# epaper-watch.net
KiCad netlist of a schematic drawn in EAGLE
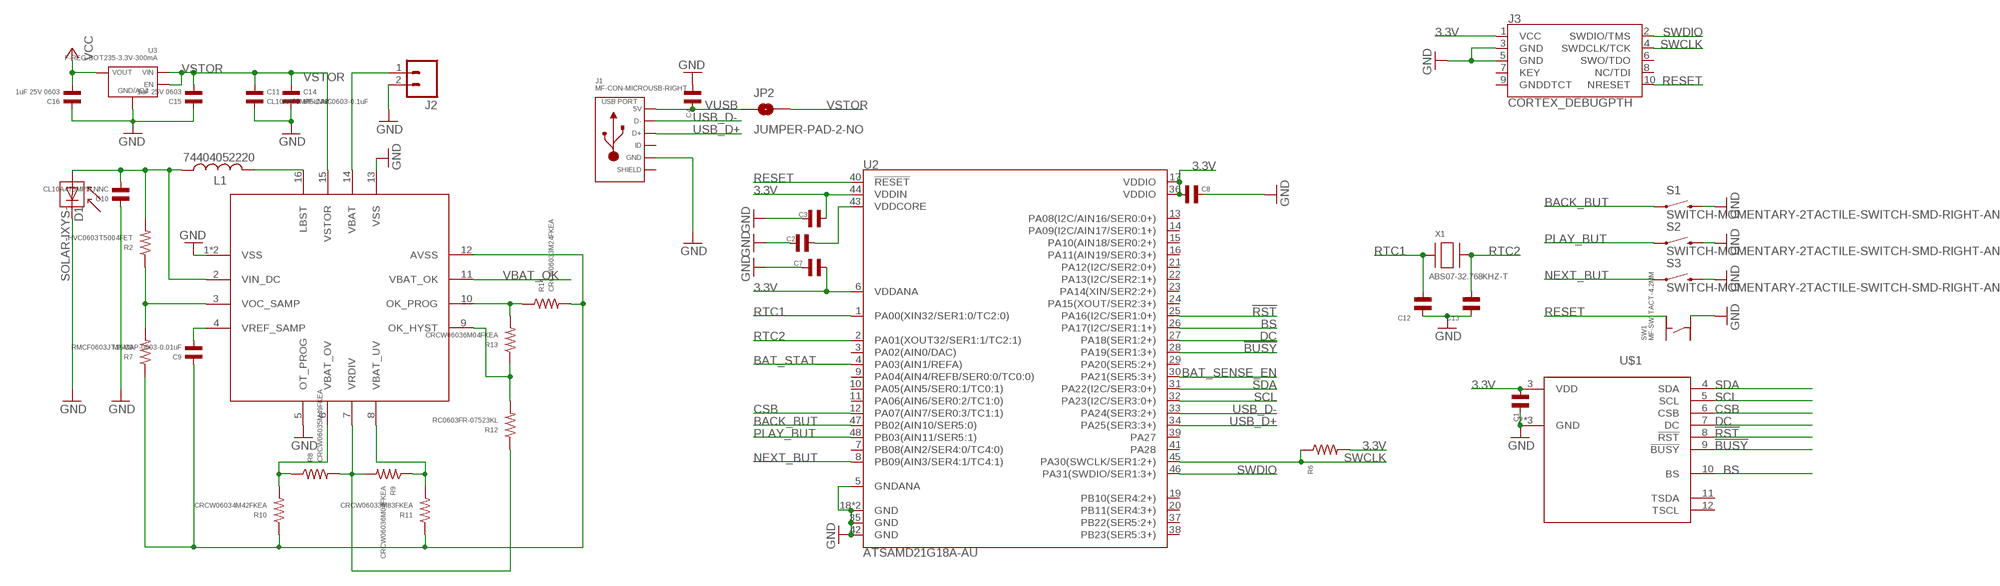
[diagram p0: schematic, sheet 1]

(export (version "E")
  (design (tool "Eeschema 10.0.6"))
  (components
    (comp (ref "C1")
      (value "0.1uF 0603")
      (footprint "eagle-import:C0603")
      (libsource (lib "eagle-import") (part "CAPACITOR_NP_0603"))
    )
    (comp (ref "C2")
      (value "1uF 0603")
      (footprint "eagle-import:C0603")
      (libsource (lib "eagle-import") (part "CAPACITOR_NP_0603"))
    )
    (comp (ref "C3")
      (value "0.1uF 0603")
      (footprint "eagle-import:C0603")
      (libsource (lib "eagle-import") (part "CAPACITOR_NP_0603"))
    )
    (comp (ref "C4")
      (value "0.1uF 0603")
      (footprint "eagle-import:C0603")
      (libsource (lib "eagle-import") (part "CAPACITOR_NP_0603"))
    )
    (comp (ref "C7")
      (value "0.1uF 0603")
      (footprint "eagle-import:C0603")
      (libsource (lib "eagle-import") (part "CAPACITOR_NP_0603"))
    )
    (comp (ref "C8")
      (value "0.1uF 0603")
      (footprint "eagle-import:C0603")
      (libsource (lib "eagle-import") (part "CAPACITOR_NP_0603"))
    )
    (comp (ref "C9")
      (value "MF-CAP-0603-0.01uF")
      (footprint "eagle-import:C0603")
      (libsource (lib "eagle-import") (part "CAPACITOR_NP_0603"))
    )
    (comp (ref "C10")
      (value "CL10A475MP5LNNC")
      (footprint "eagle-import:C0603")
      (libsource (lib "eagle-import") (part "CAPACITOR_NP_0603"))
    )
    (comp (ref "C11")
      (value "CL10A475MP5LNNC")
      (footprint "eagle-import:C0603")
      (libsource (lib "eagle-import") (part "CAPACITOR_NP_0603"))
    )
    (comp (ref "C12")
      (value "15pF")
      (footprint "eagle-import:C0603")
      (libsource (lib "eagle-import") (part "CAPACITOR_NP_0603"))
    )
    (comp (ref "C13")
      (value "15pF")
      (footprint "eagle-import:C0603")
      (libsource (lib "eagle-import") (part "CAPACITOR_NP_0603"))
    )
    (comp (ref "C14")
      (value "MF-CAP-0603-0.1uF")
      (footprint "eagle-import:C0603")
      (libsource (lib "eagle-import") (part "CAPACITOR_NP_0603"))
    )
    (comp (ref "C15")
      (value "1uF 25V 0603")
      (footprint "eagle-import:C0603")
      (libsource (lib "eagle-import") (part "CAPACITOR_NP_0603"))
    )
    (comp (ref "C16")
      (value "1uF 25V 0603")
      (footprint "eagle-import:C0603")
      (libsource (lib "eagle-import") (part "CAPACITOR_NP_0603"))
    )
    (comp (ref "D1")
      (value "SOLAR-IXYS-")
      (footprint "eagle-import:SOLARBIT-12X1")
      (libsource (lib "eagle-import") (part "SOLAR-IXYS-"))
    )
    (comp (ref "J1")
      (value "MF-CON-MICROUSB-RIGHT")
      (footprint "eagle-import:MICROUSB-RIGHT")
      (fields (field (name "HOUSEPART") "YES"))
      (libsource (lib "eagle-import") (part "USB_MICRO_RIGHT"))
    )
    (comp (ref "J2")
      (value "M02PTH")
      (footprint "eagle-import:1X02")
      (libsource (lib "eagle-import") (part "M02PTH"))
    )
    (comp (ref "J3")
      (value "CORTEX_DEBUGPTH")
      (footprint "eagle-import:2X5-PTH-1.27MM")
      (libsource (lib "eagle-import") (part "CORTEX_DEBUGPTH"))
    )
    (comp (ref "JP2")
      (value "JUMPER-PAD-2-NO")
      (footprint "eagle-import:PAD-JUMPER-2-NO_NO_SILK")
      (libsource (lib "eagle-import") (part "JUMPER-PAD-2-NO"))
    )
    (comp (ref "L1")
      (value "74404052220")
      (footprint "eagle-import:POWER-CHOKE_WE-TPC")
      (libsource (lib "eagle-import") (part "L-USWE-TPC"))
    )
    (comp (ref "R2")
      (value "HVC0603T5004FET")
      (footprint "eagle-import:R0603")
      (libsource (lib "eagle-import") (part "RESISTOR_0603"))
    )
    (comp (ref "R6")
      (value "1K")
      (footprint "eagle-import:R0603")
      (libsource (lib "eagle-import") (part "RESISTOR_0603"))
    )
    (comp (ref "R7")
      (value "RMCF0603JT15M0")
      (footprint "eagle-import:R0603")
      (libsource (lib "eagle-import") (part "RESISTOR_0603"))
    )
    (comp (ref "R8")
      (value "CRCW06035M49FKEA")
      (footprint "eagle-import:R0603")
      (libsource (lib "eagle-import") (part "RESISTOR_0603"))
    )
    (comp (ref "R9")
      (value "CRCW06036M04FKEA")
      (footprint "eagle-import:R0603")
      (libsource (lib "eagle-import") (part "RESISTOR_0603"))
    )
    (comp (ref "R10")
      (value "CRCW06034M42FKEA")
      (footprint "eagle-import:R0603")
      (libsource (lib "eagle-import") (part "RESISTOR_0603"))
    )
    (comp (ref "R11")
      (value "CRCW06033M83FKEA")
      (footprint "eagle-import:R0603")
      (libsource (lib "eagle-import") (part "RESISTOR_0603"))
    )
    (comp (ref "R12")
      (value "RC0603FR-07523KL")
      (footprint "eagle-import:R0603")
      (libsource (lib "eagle-import") (part "RESISTOR_0603"))
    )
    (comp (ref "R13")
      (value "CRCW06036M04FKEA")
      (footprint "eagle-import:R0603")
      (libsource (lib "eagle-import") (part "RESISTOR_0603"))
    )
    (comp (ref "R14")
      (value "CRCW06033M24FKEA")
      (footprint "eagle-import:R0603")
      (libsource (lib "eagle-import") (part "RESISTOR_0603"))
    )
    (comp (ref "S1")
      (value "SWITCH-MOMENTARY-2TACTILE-SWITCH-SMD-RIGHT-ANGLE")
      (footprint "eagle-import:TACTILE_SWITCH-SMD-RIGHT-ANGLE")
      (libsource (lib "eagle-import") (part "SWITCH-MOMENTARY-2TACTILE-SWITCH-SMD-RIGHT-ANGLE"))
    )
    (comp (ref "S2")
      (value "SWITCH-MOMENTARY-2TACTILE-SWITCH-SMD-RIGHT-ANGLE")
      (footprint "eagle-import:TACTILE_SWITCH-SMD-RIGHT-ANGLE")
      (libsource (lib "eagle-import") (part "SWITCH-MOMENTARY-2TACTILE-SWITCH-SMD-RIGHT-ANGLE"))
    )
    (comp (ref "S3")
      (value "SWITCH-MOMENTARY-2TACTILE-SWITCH-SMD-RIGHT-ANGLE")
      (footprint "eagle-import:TACTILE_SWITCH-SMD-RIGHT-ANGLE")
      (libsource (lib "eagle-import") (part "SWITCH-MOMENTARY-2TACTILE-SWITCH-SMD-RIGHT-ANGLE"))
    )
    (comp (ref "SW1")
      (value "MF-SW-TACT-4.2MM")
      (footprint "eagle-import:TACT4.2MM")
      (fields (field (name "HOUSEPART") "YES"))
      (libsource (lib "eagle-import") (part "TACT_4.2MM"))
    )
    (comp (ref "U$1")
      (value "GDEP011TT2")
      (footprint "eagle-import:FH26W-15S-0.3S")
      (libsource (lib "eagle-import") (part "GDEP011TT2"))
    )
    (comp (ref "U1")
      (value "BQ25504RGTT")
      (footprint "eagle-import:QFN16-3X3MM_1_1_V03")
      (libsource (lib "eagle-import") (part "BQ25504"))
    )
    (comp (ref "U2")
      (value "ATSAMD21G18A-AU")
      (footprint "eagle-import:QFN-48")
      (libsource (lib "eagle-import") (part "ATSAMD21G-M"))
    )
    (comp (ref "U3")
      (value "F-REG-SOT235-3.3V-300mA")
      (footprint "eagle-import:SOT-23-5")
      (fields (field (name "HOUSEPART") "YES"))
      (libsource (lib "eagle-import") (part "TLV70233PDBVR"))
    )
    (comp (ref "X1")
      (value "ABS07-32.768KHZ-T")
      (footprint "eagle-import:XTAL3215")
      (libsource (lib "eagle-import") (part "XTAL-3.2X1.5"))
    )
  )
  (nets
    (net (code "1") (name "/3.3V") (class "Default")
      (node (ref "C1") (pin "P$2") (pinfunction "P$2_P$2") (pintype "passive"))
      (node (ref "C3") (pin "P$2") (pinfunction "P$2_P$2") (pintype "passive"))
      (node (ref "C7") (pin "P$2") (pinfunction "P$2_P$2") (pintype "passive"))
      (node (ref "C8") (pin "P$2") (pinfunction "P$2_P$2") (pintype "passive"))
      (node (ref "J3") (pin "1") (pinfunction "VCC_1") (pintype "bidirectional"))
      (node (ref "R6") (pin "P$2") (pinfunction "P$2_P$2") (pintype "passive"))
      (node (ref "U$1") (pin "3") (pinfunction "VDD_3") (pintype "bidirectional"))
      (node (ref "U2") (pin "17") (pinfunction "VDDIO_17") (pintype "bidirectional"))
      (node (ref "U2") (pin "36") (pinfunction "VDDIO_36") (pintype "bidirectional"))
      (node (ref "U2") (pin "44") (pinfunction "VDDIN_44") (pintype "bidirectional"))
      (node (ref "U2") (pin "6") (pinfunction "VDDANA_6") (pintype "bidirectional"))
    )
    (net (code "2") (name "/BACK_BUT") (class "Default")
      (node (ref "S1") (pin "1") (pinfunction "1_1") (pintype "passive"))
      (node (ref "U2") (pin "47") (pinfunction "PB02(AIN10/SER5:0)_47") (pintype "bidirectional"))
    )
    (net (code "3") (name "/BAT_SENSE_EN") (class "Default")
      (node (ref "U2") (pin "30") (pinfunction "PA21(SER5:3+)_30") (pintype "bidirectional"))
    )
    (net (code "4") (name "/BAT_STAT") (class "Default")
      (node (ref "U2") (pin "4") (pinfunction "PA03(AIN1/REFA)_4") (pintype "bidirectional"))
    )
    (net (code "5") (name "/BS") (class "Default")
      (node (ref "U$1") (pin "10") (pinfunction "BS_10") (pintype "bidirectional"))
      (node (ref "U2") (pin "26") (pinfunction "PA17(I2C/SER1:1+)_26") (pintype "bidirectional"))
    )
    (net (code "6") (name "/CSB") (class "Default")
      (node (ref "U$1") (pin "6") (pinfunction "CSB_6") (pintype "bidirectional"))
      (node (ref "U2") (pin "12") (pinfunction "PA07(AIN7/SER0:3/TC1:1)_12") (pintype "bidirectional"))
    )
    (net (code "7") (name "/DC") (class "Default")
      (node (ref "U$1") (pin "7") (pinfunction "DC_7") (pintype "bidirectional"))
      (node (ref "U2") (pin "27") (pinfunction "PA18(SER1:2+)_27") (pintype "bidirectional"))
    )
    (net (code "8") (name "/NEXT_BUT") (class "Default")
      (node (ref "S3") (pin "1") (pinfunction "1_1") (pintype "passive"))
      (node (ref "U2") (pin "8") (pinfunction "PB09(AIN3/SER4:1/TC4:1)_8") (pintype "bidirectional"))
    )
    (net (code "9") (name "/PLAY_BUT") (class "Default")
      (node (ref "S2") (pin "1") (pinfunction "1_1") (pintype "passive"))
      (node (ref "U2") (pin "48") (pinfunction "PB03(AIN11/SER5:1)_48") (pintype "bidirectional"))
    )
    (net (code "10") (name "/RESET") (class "Default")
      (node (ref "J3") (pin "10") (pinfunction "NRESET_10") (pintype "bidirectional"))
      (node (ref "SW1") (pin "P$2") (pinfunction "P$2_P$2") (pintype "bidirectional"))
      (node (ref "U2") (pin "40") (pinfunction "~{RESET}_40") (pintype "bidirectional"))
    )
    (net (code "11") (name "/RTC1") (class "Default")
      (node (ref "C12") (pin "P$2") (pinfunction "P$2_P$2") (pintype "passive"))
      (node (ref "U2") (pin "1") (pinfunction "PA00(XIN32/SER1:0/TC2:0)_1") (pintype "bidirectional"))
      (node (ref "X1") (pin "P$1") (pinfunction "P$1_P$1") (pintype "bidirectional"))
    )
    (net (code "12") (name "/RTC2") (class "Default")
      (node (ref "C13") (pin "P$2") (pinfunction "P$2_P$2") (pintype "passive"))
      (node (ref "U2") (pin "2") (pinfunction "PA01(XOUT32/SER1:1/TC2:1)_2") (pintype "bidirectional"))
      (node (ref "X1") (pin "P$2") (pinfunction "P$2_P$2") (pintype "bidirectional"))
    )
    (net (code "13") (name "/SCL") (class "Default")
      (node (ref "U$1") (pin "5") (pinfunction "SCL_5") (pintype "bidirectional"))
      (node (ref "U2") (pin "32") (pinfunction "PA23(I2C/SER3:0+)_32") (pintype "bidirectional"))
    )
    (net (code "14") (name "/SDA") (class "Default")
      (node (ref "U$1") (pin "4") (pinfunction "SDA_4") (pintype "bidirectional"))
      (node (ref "U2") (pin "31") (pinfunction "PA22(I2C/SER3:0+)_31") (pintype "bidirectional"))
    )
    (net (code "15") (name "/SLD") (class "Default")
      (node (ref "J1") (pin "S1") (pinfunction "SLD_S1") (pintype "power_in"))
    )
    (net (code "16") (name "/SWCLK") (class "Default")
      (node (ref "J3") (pin "4") (pinfunction "SWDCLK/TCK_4") (pintype "bidirectional"))
      (node (ref "R6") (pin "P$1") (pinfunction "P$1_P$1") (pintype "passive"))
      (node (ref "U2") (pin "45") (pinfunction "PA30(SWCLK/SER1:2+)_45") (pintype "bidirectional"))
    )
    (net (code "17") (name "/SWDIO") (class "Default")
      (node (ref "J3") (pin "2") (pinfunction "SWDIO/TMS_2") (pintype "bidirectional"))
      (node (ref "U2") (pin "46") (pinfunction "PA31(SWDIO/SER1:3+)_46") (pintype "bidirectional"))
    )
    (net (code "18") (name "/USB_D+") (class "Default")
      (node (ref "J1") (pin "3") (pinfunction "D+_3") (pintype "bidirectional"))
      (node (ref "U2") (pin "34") (pinfunction "PA25(SER3:3+)_34") (pintype "bidirectional"))
    )
    (net (code "19") (name "/USB_D-") (class "Default")
      (node (ref "J1") (pin "2") (pinfunction "D-_2") (pintype "bidirectional"))
      (node (ref "U2") (pin "33") (pinfunction "PA24(SER3:2+)_33") (pintype "bidirectional"))
    )
    (net (code "20") (name "/VBAT_OK") (class "Default")
      (node (ref "U1") (pin "11") (pinfunction "VBAT_OK_11") (pintype "bidirectional"))
    )
    (net (code "21") (name "/VSTOR") (class "Default")
      (node (ref "C11") (pin "P$1") (pinfunction "P$1_P$1") (pintype "passive"))
      (node (ref "C14") (pin "P$1") (pinfunction "P$1_P$1") (pintype "passive"))
      (node (ref "C15") (pin "P$2") (pinfunction "P$2_P$2") (pintype "passive"))
      (node (ref "JP2") (pin "2") (pinfunction "2_2") (pintype "passive"))
      (node (ref "U1") (pin "15") (pinfunction "VSTOR_15") (pintype "bidirectional"))
      (node (ref "U3") (pin "P$1") (pinfunction "VIN_P$1") (pintype "bidirectional"))
      (node (ref "U3") (pin "P$3") (pinfunction "EN_P$3") (pintype "bidirectional"))
    )
    (net (code "22") (name "/VUSB") (class "Default")
      (node (ref "C4") (pin "P$1") (pinfunction "P$1_P$1") (pintype "passive"))
      (node (ref "J1") (pin "1") (pinfunction "5V_1") (pintype "power_in"))
      (node (ref "JP2") (pin "1") (pinfunction "1_1") (pintype "passive"))
    )
    (net (code "23") (name "/~{BUSY}") (class "Default")
      (node (ref "U$1") (pin "9") (pinfunction "~{BUSY}_9") (pintype "bidirectional"))
      (node (ref "U2") (pin "28") (pinfunction "PA19(SER1:3+)_28") (pintype "bidirectional"))
    )
    (net (code "24") (name "/~{RST}") (class "Default")
      (node (ref "U$1") (pin "8") (pinfunction "~{RST}_8") (pintype "bidirectional"))
      (node (ref "U2") (pin "25") (pinfunction "PA16(I2C/SER1:0+)_25") (pintype "bidirectional"))
    )
    (net (code "25") (name "GND") (class "Default")
      (node (ref "C1") (pin "P$1") (pinfunction "P$1_P$1") (pintype "passive"))
      (node (ref "C10") (pin "P$1") (pinfunction "P$1_P$1") (pintype "passive"))
      (node (ref "C11") (pin "P$2") (pinfunction "P$2_P$2") (pintype "passive"))
      (node (ref "C12") (pin "P$1") (pinfunction "P$1_P$1") (pintype "passive"))
      (node (ref "C13") (pin "P$1") (pinfunction "P$1_P$1") (pintype "passive"))
      (node (ref "C14") (pin "P$2") (pinfunction "P$2_P$2") (pintype "passive"))
      (node (ref "C15") (pin "P$1") (pinfunction "P$1_P$1") (pintype "passive"))
      (node (ref "C16") (pin "P$1") (pinfunction "P$1_P$1") (pintype "passive"))
      (node (ref "C2") (pin "P$2") (pinfunction "P$2_P$2") (pintype "passive"))
      (node (ref "C3") (pin "P$1") (pinfunction "P$1_P$1") (pintype "passive"))
      (node (ref "C4") (pin "P$2") (pinfunction "P$2_P$2") (pintype "passive"))
      (node (ref "C7") (pin "P$1") (pinfunction "P$1_P$1") (pintype "passive"))
      (node (ref "C8") (pin "P$1") (pinfunction "P$1_P$1") (pintype "passive"))
      (node (ref "D1") (pin "-") (pinfunction "C_-") (pintype "passive"))
      (node (ref "J1") (pin "5") (pinfunction "GND_5") (pintype "power_in"))
      (node (ref "J2") (pin "2") (pinfunction "2_2") (pintype "passive"))
      (node (ref "J3") (pin "3") (pinfunction "GND_3") (pintype "bidirectional"))
      (node (ref "J3") (pin "5") (pinfunction "GND_5") (pintype "bidirectional"))
      (node (ref "S1") (pin "2") (pinfunction "2_2") (pintype "passive"))
      (node (ref "S2") (pin "2") (pinfunction "2_2") (pintype "passive"))
      (node (ref "S3") (pin "2") (pinfunction "2_2") (pintype "passive"))
      (node (ref "SW1") (pin "P$4") (pinfunction "P$4_P$4") (pintype "bidirectional"))
      (node (ref "U$1") (pin "2") (pinfunction "GND_2") (pintype "bidirectional"))
      (node (ref "U$1") (pin "EXP1") (pinfunction "GND_EXP1") (pintype "bidirectional"))
      (node (ref "U$1") (pin "EXP2") (pinfunction "GND_EXP2") (pintype "bidirectional"))
      (node (ref "U1") (pin "1") (pinfunction "VSS_1") (pintype "bidirectional"))
      (node (ref "U1") (pin "13") (pinfunction "VSS_13") (pintype "bidirectional"))
      (node (ref "U1") (pin "5") (pinfunction "OT_PROG_5") (pintype "bidirectional"))
      (node (ref "U1") (pin "EXT") (pinfunction "VSS_EXT") (pintype "bidirectional"))
      (node (ref "U2") (pin "18") (pinfunction "GND_18") (pintype "bidirectional"))
      (node (ref "U2") (pin "35") (pinfunction "GND_35") (pintype "bidirectional"))
      (node (ref "U2") (pin "42") (pinfunction "GND_42") (pintype "bidirectional"))
      (node (ref "U2") (pin "5") (pinfunction "GNDANA_5") (pintype "bidirectional"))
      (node (ref "U2") (pin "EP") (pinfunction "GND_EP") (pintype "bidirectional"))
      (node (ref "U3") (pin "P$2") (pinfunction "GND/ADJ_P$2") (pintype "bidirectional"))
    )
    (net (code "26") (name "Net-(D1-A)") (class "Default")
      (node (ref "C10") (pin "P$2") (pinfunction "P$2_P$2") (pintype "passive"))
      (node (ref "D1") (pin "+") (pinfunction "A_+") (pintype "passive"))
      (node (ref "L1") (pin "1") (pinfunction "1_1") (pintype "passive"))
      (node (ref "R2") (pin "P$2") (pinfunction "P$2_P$2") (pintype "passive"))
      (node (ref "U1") (pin "2") (pinfunction "VIN_DC_2") (pintype "bidirectional"))
    )
    (net (code "27") (name "Net-(U1-AVSS)") (class "Default")
      (node (ref "C9") (pin "P$1") (pinfunction "P$1_P$1") (pintype "passive"))
      (node (ref "R10") (pin "P$1") (pinfunction "P$1_P$1") (pintype "passive"))
      (node (ref "R11") (pin "P$1") (pinfunction "P$1_P$1") (pintype "passive"))
      (node (ref "R14") (pin "P$2") (pinfunction "P$2_P$2") (pintype "passive"))
      (node (ref "R7") (pin "P$1") (pinfunction "P$1_P$1") (pintype "passive"))
      (node (ref "U1") (pin "12") (pinfunction "AVSS_12") (pintype "bidirectional"))
    )
    (net (code "28") (name "Net-(U1-LBST)") (class "Default")
      (node (ref "L1") (pin "2") (pinfunction "2_2") (pintype "passive"))
      (node (ref "U1") (pin "16") (pinfunction "LBST_16") (pintype "bidirectional"))
    )
    (net (code "29") (name "Net-(U1-OK_HYST)") (class "Default")
      (node (ref "R12") (pin "P$2") (pinfunction "P$2_P$2") (pintype "passive"))
      (node (ref "R13") (pin "P$1") (pinfunction "P$1_P$1") (pintype "passive"))
      (node (ref "U1") (pin "9") (pinfunction "OK_HYST_9") (pintype "bidirectional"))
    )
    (net (code "30") (name "Net-(U1-OK_PROG)") (class "Default")
      (node (ref "R13") (pin "P$2") (pinfunction "P$2_P$2") (pintype "passive"))
      (node (ref "R14") (pin "P$1") (pinfunction "P$1_P$1") (pintype "passive"))
      (node (ref "U1") (pin "10") (pinfunction "OK_PROG_10") (pintype "bidirectional"))
    )
    (net (code "31") (name "Net-(U1-VBAT)") (class "Default")
      (node (ref "J2") (pin "1") (pinfunction "1_1") (pintype "passive"))
      (node (ref "U1") (pin "14") (pinfunction "VBAT_14") (pintype "bidirectional"))
    )
    (net (code "32") (name "Net-(U1-VBAT_OV)") (class "Default")
      (node (ref "R10") (pin "P$2") (pinfunction "P$2_P$2") (pintype "passive"))
      (node (ref "R8") (pin "P$1") (pinfunction "P$1_P$1") (pintype "passive"))
      (node (ref "U1") (pin "6") (pinfunction "VBAT_OV_6") (pintype "bidirectional"))
    )
    (net (code "33") (name "Net-(U1-VBAT_UV)") (class "Default")
      (node (ref "R11") (pin "P$2") (pinfunction "P$2_P$2") (pintype "passive"))
      (node (ref "R9") (pin "P$1") (pinfunction "P$1_P$1") (pintype "passive"))
      (node (ref "U1") (pin "8") (pinfunction "VBAT_UV_8") (pintype "bidirectional"))
    )
    (net (code "34") (name "Net-(U1-VOC_SAMP)") (class "Default")
      (node (ref "R2") (pin "P$1") (pinfunction "P$1_P$1") (pintype "passive"))
      (node (ref "R7") (pin "P$2") (pinfunction "P$2_P$2") (pintype "passive"))
      (node (ref "U1") (pin "3") (pinfunction "VOC_SAMP_3") (pintype "bidirectional"))
    )
    (net (code "35") (name "Net-(U1-VRDIV)") (class "Default")
      (node (ref "R12") (pin "P$1") (pinfunction "P$1_P$1") (pintype "passive"))
      (node (ref "R8") (pin "P$2") (pinfunction "P$2_P$2") (pintype "passive"))
      (node (ref "R9") (pin "P$2") (pinfunction "P$2_P$2") (pintype "passive"))
      (node (ref "U1") (pin "7") (pinfunction "VRDIV_7") (pintype "bidirectional"))
    )
    (net (code "36") (name "Net-(U1-VREF_SAMP)") (class "Default")
      (node (ref "C9") (pin "P$2") (pinfunction "P$2_P$2") (pintype "passive"))
      (node (ref "U1") (pin "4") (pinfunction "VREF_SAMP_4") (pintype "bidirectional"))
    )
    (net (code "37") (name "Net-(U2-VDDCORE)") (class "Default")
      (node (ref "C2") (pin "P$1") (pinfunction "P$1_P$1") (pintype "passive"))
      (node (ref "U2") (pin "43") (pinfunction "VDDCORE_43") (pintype "bidirectional"))
    )
    (net (code "38") (name "VCC") (class "Default")
      (node (ref "C16") (pin "P$2") (pinfunction "P$2_P$2") (pintype "passive"))
      (node (ref "U3") (pin "P$5") (pinfunction "VOUT_P$5") (pintype "bidirectional"))
    )
    (net (code "39") (name "unconnected-(J1-ID-Pad4)") (class "Default")
      (node (ref "J1") (pin "4") (pinfunction "ID_4") (pintype "bidirectional"))
    )
    (net (code "40") (name "unconnected-(J3-GNDDTCT-Pad9)") (class "Default")
      (node (ref "J3") (pin "9") (pinfunction "GNDDTCT_9") (pintype "bidirectional"))
    )
    (net (code "41") (name "unconnected-(J3-KEY-Pad7)") (class "Default")
      (node (ref "J3") (pin "7") (pinfunction "KEY_7") (pintype "bidirectional"))
    )
    (net (code "42") (name "unconnected-(J3-NC{slash}TDI-Pad8)") (class "Default")
      (node (ref "J3") (pin "8") (pinfunction "NC/TDI_8") (pintype "bidirectional"))
    )
    (net (code "43") (name "unconnected-(J3-SWO{slash}TDO-Pad6)") (class "Default")
      (node (ref "J3") (pin "6") (pinfunction "SWO/TDO_6") (pintype "bidirectional"))
    )
    (net (code "44") (name "unconnected-(SW1-PadP$1)") (class "Default")
      (node (ref "SW1") (pin "P$1") (pinfunction "P$1_P$1") (pintype "bidirectional"))
    )
    (net (code "45") (name "unconnected-(SW1-PadP$3)") (class "Default")
      (node (ref "SW1") (pin "P$3") (pinfunction "P$3_P$3") (pintype "bidirectional"))
    )
    (net (code "46") (name "unconnected-(U$1-TSCL-Pad12)") (class "Default")
      (node (ref "U$1") (pin "12") (pinfunction "TSCL_12") (pintype "bidirectional"))
    )
    (net (code "47") (name "unconnected-(U$1-TSDA-Pad11)") (class "Default")
      (node (ref "U$1") (pin "11") (pinfunction "TSDA_11") (pintype "bidirectional"))
    )
    (net (code "48") (name "unconnected-(U2-PA02(AIN0{slash}DAC)-Pad3)") (class "Default")
      (node (ref "U2") (pin "3") (pinfunction "PA02(AIN0/DAC)_3") (pintype "bidirectional"))
    )
    (net (code "49") (name "unconnected-(U2-PA04(AIN4{slash}REFB{slash}SER0:0{slash}TC0:0)-Pad9)") (class "Default")
      (node (ref "U2") (pin "9") (pinfunction "PA04(AIN4/REFB/SER0:0/TC0:0)_9") (pintype "bidirectional"))
    )
    (net (code "50") (name "unconnected-(U2-PA05(AIN5{slash}SER0:1{slash}TC0:1)-Pad10)") (class "Default")
      (node (ref "U2") (pin "10") (pinfunction "PA05(AIN5/SER0:1/TC0:1)_10") (pintype "bidirectional"))
    )
    (net (code "51") (name "unconnected-(U2-PA06(AIN6{slash}SER0:2{slash}TC1:0)-Pad11)") (class "Default")
      (node (ref "U2") (pin "11") (pinfunction "PA06(AIN6/SER0:2/TC1:0)_11") (pintype "bidirectional"))
    )
    (net (code "52") (name "unconnected-(U2-PA08(I2C{slash}AIN16{slash}SER0:0+)-Pad13)") (class "Default")
      (node (ref "U2") (pin "13") (pinfunction "PA08(I2C/AIN16/SER0:0+)_13") (pintype "bidirectional"))
    )
    (net (code "53") (name "unconnected-(U2-PA09(I2C{slash}AIN17{slash}SER0:1+)-Pad14)") (class "Default")
      (node (ref "U2") (pin "14") (pinfunction "PA09(I2C/AIN17/SER0:1+)_14") (pintype "bidirectional"))
    )
    (net (code "54") (name "unconnected-(U2-PA10(AIN18{slash}SER0:2+)-Pad15)") (class "Default")
      (node (ref "U2") (pin "15") (pinfunction "PA10(AIN18/SER0:2+)_15") (pintype "bidirectional"))
    )
    (net (code "55") (name "unconnected-(U2-PA11(AIN19{slash}SER0:3+)-Pad16)") (class "Default")
      (node (ref "U2") (pin "16") (pinfunction "PA11(AIN19/SER0:3+)_16") (pintype "bidirectional"))
    )
    (net (code "56") (name "unconnected-(U2-PA12(I2C{slash}SER2:0+)-Pad21)") (class "Default")
      (node (ref "U2") (pin "21") (pinfunction "PA12(I2C/SER2:0+)_21") (pintype "bidirectional"))
    )
    (net (code "57") (name "unconnected-(U2-PA13(I2C{slash}SER2:1+)-Pad22)") (class "Default")
      (node (ref "U2") (pin "22") (pinfunction "PA13(I2C/SER2:1+)_22") (pintype "bidirectional"))
    )
    (net (code "58") (name "unconnected-(U2-PA14(XIN{slash}SER2:2+)-Pad23)") (class "Default")
      (node (ref "U2") (pin "23") (pinfunction "PA14(XIN/SER2:2+)_23") (pintype "bidirectional"))
    )
    (net (code "59") (name "unconnected-(U2-PA15(XOUT{slash}SER2:3+)-Pad24)") (class "Default")
      (node (ref "U2") (pin "24") (pinfunction "PA15(XOUT/SER2:3+)_24") (pintype "bidirectional"))
    )
    (net (code "60") (name "unconnected-(U2-PA20(SER5:2+)-Pad29)") (class "Default")
      (node (ref "U2") (pin "29") (pinfunction "PA20(SER5:2+)_29") (pintype "bidirectional"))
    )
    (net (code "61") (name "unconnected-(U2-PA27-Pad39)") (class "Default")
      (node (ref "U2") (pin "39") (pinfunction "PA27_39") (pintype "bidirectional"))
    )
    (net (code "62") (name "unconnected-(U2-PA28-Pad41)") (class "Default")
      (node (ref "U2") (pin "41") (pinfunction "PA28_41") (pintype "bidirectional"))
    )
    (net (code "63") (name "unconnected-(U2-PB08(AIN2{slash}SER4:0{slash}TC4:0)-Pad7)") (class "Default")
      (node (ref "U2") (pin "7") (pinfunction "PB08(AIN2/SER4:0/TC4:0)_7") (pintype "bidirectional"))
    )
    (net (code "64") (name "unconnected-(U2-PB10(SER4:2+)-Pad19)") (class "Default")
      (node (ref "U2") (pin "19") (pinfunction "PB10(SER4:2+)_19") (pintype "bidirectional"))
    )
    (net (code "65") (name "unconnected-(U2-PB11(SER4:3+)-Pad20)") (class "Default")
      (node (ref "U2") (pin "20") (pinfunction "PB11(SER4:3+)_20") (pintype "bidirectional"))
    )
    (net (code "66") (name "unconnected-(U2-PB22(SER5:2+)-Pad37)") (class "Default")
      (node (ref "U2") (pin "37") (pinfunction "PB22(SER5:2+)_37") (pintype "bidirectional"))
    )
    (net (code "67") (name "unconnected-(U2-PB23(SER5:3+)-Pad38)") (class "Default")
      (node (ref "U2") (pin "38") (pinfunction "PB23(SER5:3+)_38") (pintype "bidirectional"))
    )
  )
)
